# MotionDetector.net
KiCad netlist of a schematic drawn in Altium Designer
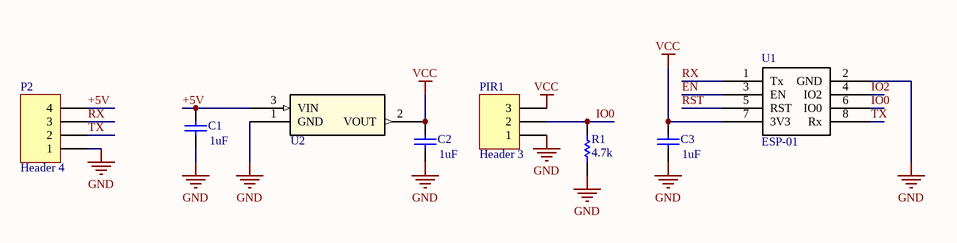
[diagram p0: MotionDetector.SchDoc]

(export (version "E")
  (design (tool "Eeschema 10.0.6"))
  (components
    (comp (ref "C1")
      (value "1uF")
      (footprint "CAP_0804")
      (description "Capacitor")
      (fields (field (name "Comment") "Cap") (field (name "PUBLISHER") "Altium Limited"))
      (libsource (lib "Miscellaneous Devices") (part "Cap"))
    )
    (comp (ref "C2")
      (value "1uF")
      (footprint "CAP_0804")
      (description "Capacitor")
      (fields (field (name "Comment") "Cap") (field (name "PUBLISHER") "Altium Limited"))
      (libsource (lib "Miscellaneous Devices") (part "Cap"))
    )
    (comp (ref "C3")
      (value "1uF")
      (footprint "CAP_0804")
      (description "Capacitor")
      (fields (field (name "Comment") "Cap") (field (name "PUBLISHER") "Altium Limited"))
      (libsource (lib "Miscellaneous Devices") (part "Cap"))
    )
    (comp (ref "P2")
      (value "Header 4")
      (footprint "HDR1X4")
      (description "Header, 4-Pin")
      (fields (field (name "PUBLISHER") "Altium Limited"))
      (libsource (lib "Miscellaneous Connectors") (part "Header 4"))
    )
    (comp (ref "PIR1")
      (value "Header 3")
      (footprint "HDR1X3")
      (description "Header, 3-Pin")
      (fields (field (name "PUBLISHER") "Altium Limited"))
      (libsource (lib "Miscellaneous Connectors") (part "Header 3"))
    )
    (comp (ref "R1")
      (value "4.7k")
      (footprint "RES_0804_panasonic")
      (description "Resistor")
      (fields (field (name "Comment") "Res1") (field (name "PUBLISHER") "Altium Limited"))
      (libsource (lib "Miscellaneous Devices") (part "Res1"))
    )
    (comp (ref "U1")
      (value "ESP-01")
      (footprint "ESP-01")
      (libsource (lib "MotionDetectorSchematicLib") (part "ESP-01"))
    )
    (comp (ref "U2")
      (value "Voltage Reg")
      (footprint "SOT-23")
      (fields (field (name "MANUFACTURER_PART_NUMBER") "AP2120N-3.3TRG1"))
      (libsource (lib "MotionDetectorSchematicLib") (part "AP2120N-3.3TRG1"))
    )
  )
  (nets
    (net (code "1") (name "/+5V") (class "Default")
      (node (ref "C1") (pin "2") (pinfunction "2_2") (pintype "passive"))
      (node (ref "P2") (pin "4") (pinfunction "4_4") (pintype "passive"))
      (node (ref "U2") (pin "3") (pinfunction "VIN_3") (pintype "input"))
    )
    (net (code "2") (name "/EN") (class "Default")
      (node (ref "U1") (pin "3") (pinfunction "EN_3") (pintype "passive"))
    )
    (net (code "3") (name "/IO0") (class "Default")
      (node (ref "PIR1") (pin "2") (pinfunction "2_2") (pintype "passive"))
      (node (ref "R1") (pin "2") (pinfunction "2_2") (pintype "passive"))
      (node (ref "U1") (pin "6") (pinfunction "IO0_6") (pintype "passive"))
    )
    (net (code "4") (name "/IO2") (class "Default")
      (node (ref "U1") (pin "4") (pinfunction "IO2_4") (pintype "passive"))
    )
    (net (code "5") (name "/RST") (class "Default")
      (node (ref "U1") (pin "5") (pinfunction "RST_5") (pintype "passive"))
    )
    (net (code "6") (name "/RX") (class "Default")
      (node (ref "P2") (pin "3") (pinfunction "3_3") (pintype "passive"))
      (node (ref "U1") (pin "1") (pinfunction "Tx_1") (pintype "passive"))
    )
    (net (code "7") (name "/TX") (class "Default")
      (node (ref "P2") (pin "2") (pinfunction "2_2") (pintype "passive"))
      (node (ref "U1") (pin "8") (pinfunction "Rx_8") (pintype "passive"))
    )
    (net (code "8") (name "GND") (class "Default")
      (node (ref "C1") (pin "1") (pinfunction "1_1") (pintype "passive"))
      (node (ref "C2") (pin "1") (pinfunction "1_1") (pintype "passive"))
      (node (ref "C3") (pin "1") (pinfunction "1_1") (pintype "passive"))
      (node (ref "P2") (pin "1") (pinfunction "1_1") (pintype "passive"))
      (node (ref "PIR1") (pin "1") (pinfunction "1_1") (pintype "passive"))
      (node (ref "R1") (pin "1") (pinfunction "1_1") (pintype "passive"))
      (node (ref "U1") (pin "2") (pinfunction "GND_2") (pintype "passive"))
      (node (ref "U2") (pin "1") (pinfunction "GND_1") (pintype "power_in"))
    )
    (net (code "9") (name "VCC") (class "Default")
      (node (ref "C2") (pin "2") (pinfunction "2_2") (pintype "passive"))
      (node (ref "C3") (pin "2") (pinfunction "2_2") (pintype "passive"))
      (node (ref "PIR1") (pin "3") (pinfunction "3_3") (pintype "passive"))
      (node (ref "U1") (pin "7") (pinfunction "3V3_7") (pintype "passive"))
      (node (ref "U2") (pin "2") (pinfunction "VOUT_2") (pintype "output"))
    )
  )
)
